# ATMega1284p.net
KiCad netlist of a schematic drawn in Altium Designer
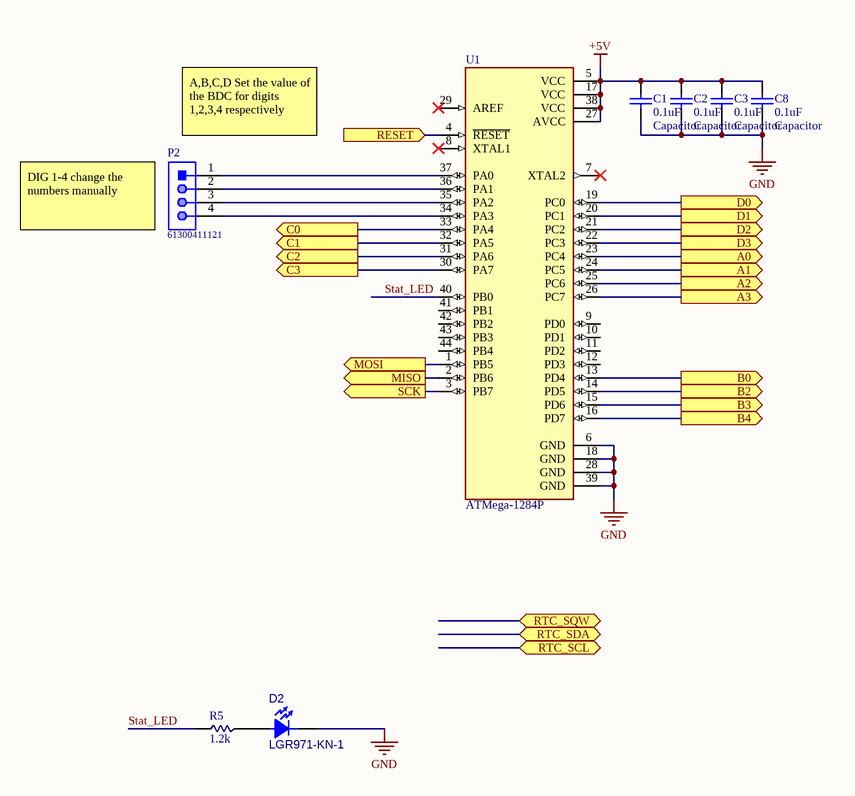
[diagram p0: ATMega1284p.SchDoc]

(export (version "E")
  (design (tool "Eeschema 10.0.6"))
  (components
    (comp (ref "C1")
      (value "0.1uF")
      (footprint "FOOTPRINT-1206-GEN")
      (description "CAP CER 0.1UF 50V X7R 1206")
      (fields
        (field (name "PART NUMBER") "1276-7034-1-ND")
        (field (name "TYPE") "Capacitor")
        (field (name "Comment") "Capacitor - 0.1uF - 1206")
        (field (name "PUBLISHER") "Altium Limited")
      )
      (libsource (lib "University of California Riverside - FSAE") (part "Symbol"))
    )
    (comp (ref "C2")
      (value "0.1uF")
      (footprint "FOOTPRINT-1206-GEN")
      (description "CAP CER 0.1UF 50V X7R 1206")
      (fields
        (field (name "PART NUMBER") "1276-7034-1-ND")
        (field (name "TYPE") "Capacitor")
        (field (name "Comment") "Capacitor - 0.1uF - 1206")
        (field (name "PUBLISHER") "Altium Limited")
      )
      (libsource (lib "University of California Riverside - FSAE") (part "Symbol"))
    )
    (comp (ref "C3")
      (value "0.1uF")
      (footprint "FOOTPRINT-1206-GEN")
      (description "CAP CER 0.1UF 50V X7R 1206")
      (fields
        (field (name "PART NUMBER") "1276-7034-1-ND")
        (field (name "TYPE") "Capacitor")
        (field (name "Comment") "Capacitor - 0.1uF - 1206")
        (field (name "PUBLISHER") "Altium Limited")
      )
      (libsource (lib "University of California Riverside - FSAE") (part "Symbol"))
    )
    (comp (ref "C8")
      (value "0.1uF")
      (footprint "FOOTPRINT-1206-GEN")
      (description "CAP CER 0.1UF 50V X7R 1206")
      (fields
        (field (name "PART NUMBER") "1276-7034-1-ND")
        (field (name "TYPE") "Capacitor")
        (field (name "Comment") "Capacitor - 0.1uF - 1206")
        (field (name "PUBLISHER") "Altium Limited")
      )
      (libsource (lib "University of California Riverside - FSAE") (part "Symbol"))
    )
    (comp (ref "D2")
      (value "LGR971-KN-1")
      (footprint "FOOTPRINT-OSRAM-CHIPLED-0805-1A2K")
      (description "LED Uni-Color Green 572nm 2-Pin Chip 0805(2012Metric) T/R")
      (fields (field (name "PART NUMBER") "475-1410-1-ND"))
      (libsource (lib "") (part "Symbol_1"))
    )
    (comp (ref "P2")
      (value "61300411121")
      (footprint "61300411121")
      (description "THT Vertical Pin Header WR-PHD, Pitch 2.54 mm, Single Row, 4 pins")
      (fields (field (name "MANUFACTURER") "Wurth Elektronik") (field (name "PUBLISHER") "WurthElektronik"))
      (libsource (lib "Altium Content Vault") (part "WE-CN-1P-M-R4"))
    )
    (comp (ref "R5")
      (value "1.2k")
      (footprint "FOOTPRINT-0805-GEN")
      (description "Res Thick Film 0805 1.2K Ohm 1% 0.125W ±100ppm/°C Molded SMD Paper T/R")
      (fields (field (name "Comment") "RMCF0805FT1K20"))
      (libsource (lib "") (part "Symbol_2"))
    )
    (comp (ref "U1")
      (value "ATMega-1284P")
      (footprint "QFP80P1200X1200X120-44N")
      (libsource (lib "HV_LIB") (part "ATMega-1284P"))
    )
  )
  (nets
    (net (code "1") (name "+5V") (class "Default")
      (node (ref "C1") (pin "2") (pinfunction "2_2") (pintype "passive"))
      (node (ref "C2") (pin "2") (pinfunction "2_2") (pintype "passive"))
      (node (ref "C3") (pin "2") (pinfunction "2_2") (pintype "passive"))
      (node (ref "C8") (pin "2") (pinfunction "2_2") (pintype "passive"))
      (node (ref "U1") (pin "17") (pinfunction "VCC_17") (pintype "power_in"))
      (node (ref "U1") (pin "27") (pinfunction "AVCC_27") (pintype "power_in"))
      (node (ref "U1") (pin "38") (pinfunction "VCC_38") (pintype "power_in"))
      (node (ref "U1") (pin "5") (pinfunction "VCC_5") (pintype "power_in"))
    )
    (net (code "2") (name "/A0") (class "Default")
      (node (ref "U1") (pin "23") (pinfunction "PC4_23") (pintype "bidirectional"))
    )
    (net (code "3") (name "/A1") (class "Default")
      (node (ref "U1") (pin "24") (pinfunction "PC5_24") (pintype "bidirectional"))
    )
    (net (code "4") (name "/A2") (class "Default")
      (node (ref "U1") (pin "25") (pinfunction "PC6_25") (pintype "bidirectional"))
    )
    (net (code "5") (name "/A3") (class "Default")
      (node (ref "U1") (pin "26") (pinfunction "PC7_26") (pintype "bidirectional"))
    )
    (net (code "6") (name "/B0") (class "Default")
      (node (ref "U1") (pin "13") (pinfunction "PD4_13") (pintype "bidirectional"))
    )
    (net (code "7") (name "/B2") (class "Default")
      (node (ref "U1") (pin "14") (pinfunction "PD5_14") (pintype "bidirectional"))
    )
    (net (code "8") (name "/B3") (class "Default")
      (node (ref "U1") (pin "15") (pinfunction "PD6_15") (pintype "bidirectional"))
    )
    (net (code "9") (name "/B4") (class "Default")
      (node (ref "U1") (pin "16") (pinfunction "PD7_16") (pintype "bidirectional"))
    )
    (net (code "10") (name "/C0") (class "Default")
      (node (ref "U1") (pin "33") (pinfunction "PA4_33") (pintype "bidirectional"))
    )
    (net (code "11") (name "/C1") (class "Default")
      (node (ref "U1") (pin "32") (pinfunction "PA5_32") (pintype "bidirectional"))
    )
    (net (code "12") (name "/C2") (class "Default")
      (node (ref "U1") (pin "31") (pinfunction "PA6_31") (pintype "bidirectional"))
    )
    (net (code "13") (name "/C3") (class "Default")
      (node (ref "U1") (pin "30") (pinfunction "PA7_30") (pintype "bidirectional"))
    )
    (net (code "14") (name "/D0") (class "Default")
      (node (ref "U1") (pin "19") (pinfunction "PC0_19") (pintype "bidirectional"))
    )
    (net (code "15") (name "/D1") (class "Default")
      (node (ref "U1") (pin "20") (pinfunction "PC1_20") (pintype "bidirectional"))
    )
    (net (code "16") (name "/D2") (class "Default")
      (node (ref "U1") (pin "21") (pinfunction "PC2_21") (pintype "bidirectional"))
    )
    (net (code "17") (name "/D3") (class "Default")
      (node (ref "U1") (pin "22") (pinfunction "PC3_22") (pintype "bidirectional"))
    )
    (net (code "18") (name "/MISO") (class "Default")
      (node (ref "U1") (pin "2") (pinfunction "PB6_2") (pintype "bidirectional"))
    )
    (net (code "19") (name "/MOSI") (class "Default")
      (node (ref "U1") (pin "1") (pinfunction "PB5_1") (pintype "bidirectional"))
    )
    (net (code "20") (name "/RESET") (class "Default")
      (node (ref "U1") (pin "4") (pinfunction "~{RESET}_4") (pintype "input"))
    )
    (net (code "24") (name "/SCK") (class "Default")
      (node (ref "U1") (pin "3") (pinfunction "PB7_3") (pintype "bidirectional"))
    )
    (net (code "25") (name "/Stat_LED") (class "Default")
      (node (ref "R5") (pin "2") (pinfunction "2_2") (pintype "passive"))
      (node (ref "U1") (pin "40") (pinfunction "PB0_40") (pintype "bidirectional"))
    )
    (net (code "26") (name "GND") (class "Default")
      (node (ref "C1") (pin "1") (pinfunction "1_1") (pintype "passive"))
      (node (ref "C2") (pin "1") (pinfunction "1_1") (pintype "passive"))
      (node (ref "C3") (pin "1") (pinfunction "1_1") (pintype "passive"))
      (node (ref "C8") (pin "1") (pinfunction "1_1") (pintype "passive"))
      (node (ref "D2") (pin "2") (pinfunction "K_2") (pintype "passive"))
      (node (ref "U1") (pin "18") (pinfunction "GND_18") (pintype "power_in"))
      (node (ref "U1") (pin "28") (pinfunction "GND_28") (pintype "power_in"))
      (node (ref "U1") (pin "39") (pinfunction "GND_39") (pintype "power_in"))
      (node (ref "U1") (pin "6") (pinfunction "GND_6") (pintype "power_in"))
    )
    (net (code "27") (name "Net-(D2-A)") (class "Default")
      (node (ref "D2") (pin "1") (pinfunction "A_1") (pintype "passive"))
      (node (ref "R5") (pin "1") (pinfunction "1_1") (pintype "passive"))
    )
    (net (code "28") (name "Net-(U1-PA0)") (class "Default")
      (node (ref "P2") (pin "1") (pinfunction "1_1") (pintype "passive"))
      (node (ref "U1") (pin "37") (pinfunction "PA0_37") (pintype "bidirectional"))
    )
    (net (code "29") (name "Net-(U1-PA1)") (class "Default")
      (node (ref "P2") (pin "2") (pinfunction "2_2") (pintype "passive"))
      (node (ref "U1") (pin "36") (pinfunction "PA1_36") (pintype "bidirectional"))
    )
    (net (code "30") (name "Net-(U1-PA2)") (class "Default")
      (node (ref "P2") (pin "3") (pinfunction "3_3") (pintype "passive"))
      (node (ref "U1") (pin "35") (pinfunction "PA2_35") (pintype "bidirectional"))
    )
    (net (code "31") (name "Net-(U1-PA3)") (class "Default")
      (node (ref "P2") (pin "4") (pinfunction "4_4") (pintype "passive"))
      (node (ref "U1") (pin "34") (pinfunction "PA3_34") (pintype "bidirectional"))
    )
    (net (code "32") (name "unconnected-(U1-AREF-Pad29)") (class "Default")
      (node (ref "U1") (pin "29") (pinfunction "AREF_29") (pintype "input+no_connect"))
    )
    (net (code "33") (name "unconnected-(U1-PB1-Pad41)") (class "Default")
      (node (ref "U1") (pin "41") (pinfunction "PB1_41") (pintype "bidirectional"))
    )
    (net (code "34") (name "unconnected-(U1-PB2-Pad42)") (class "Default")
      (node (ref "U1") (pin "42") (pinfunction "PB2_42") (pintype "bidirectional"))
    )
    (net (code "35") (name "unconnected-(U1-PB3-Pad43)") (class "Default")
      (node (ref "U1") (pin "43") (pinfunction "PB3_43") (pintype "bidirectional"))
    )
    (net (code "36") (name "unconnected-(U1-PB4-Pad44)") (class "Default")
      (node (ref "U1") (pin "44") (pinfunction "PB4_44") (pintype "bidirectional"))
    )
    (net (code "37") (name "unconnected-(U1-PD0-Pad9)") (class "Default")
      (node (ref "U1") (pin "9") (pinfunction "PD0_9") (pintype "bidirectional"))
    )
    (net (code "38") (name "unconnected-(U1-PD1-Pad10)") (class "Default")
      (node (ref "U1") (pin "10") (pinfunction "PD1_10") (pintype "bidirectional"))
    )
    (net (code "39") (name "unconnected-(U1-PD2-Pad11)") (class "Default")
      (node (ref "U1") (pin "11") (pinfunction "PD2_11") (pintype "bidirectional"))
    )
    (net (code "40") (name "unconnected-(U1-PD3-Pad12)") (class "Default")
      (node (ref "U1") (pin "12") (pinfunction "PD3_12") (pintype "bidirectional"))
    )
    (net (code "41") (name "unconnected-(U1-XTAL1-Pad8)") (class "Default")
      (node (ref "U1") (pin "8") (pinfunction "XTAL1_8") (pintype "input+no_connect"))
    )
    (net (code "42") (name "unconnected-(U1-XTAL2-Pad7)") (class "Default")
      (node (ref "U1") (pin "7") (pinfunction "XTAL2_7") (pintype "output+no_connect"))
    )
  )
)
